# IR_remote.net
KiCad netlist of a schematic drawn in Altium Designer
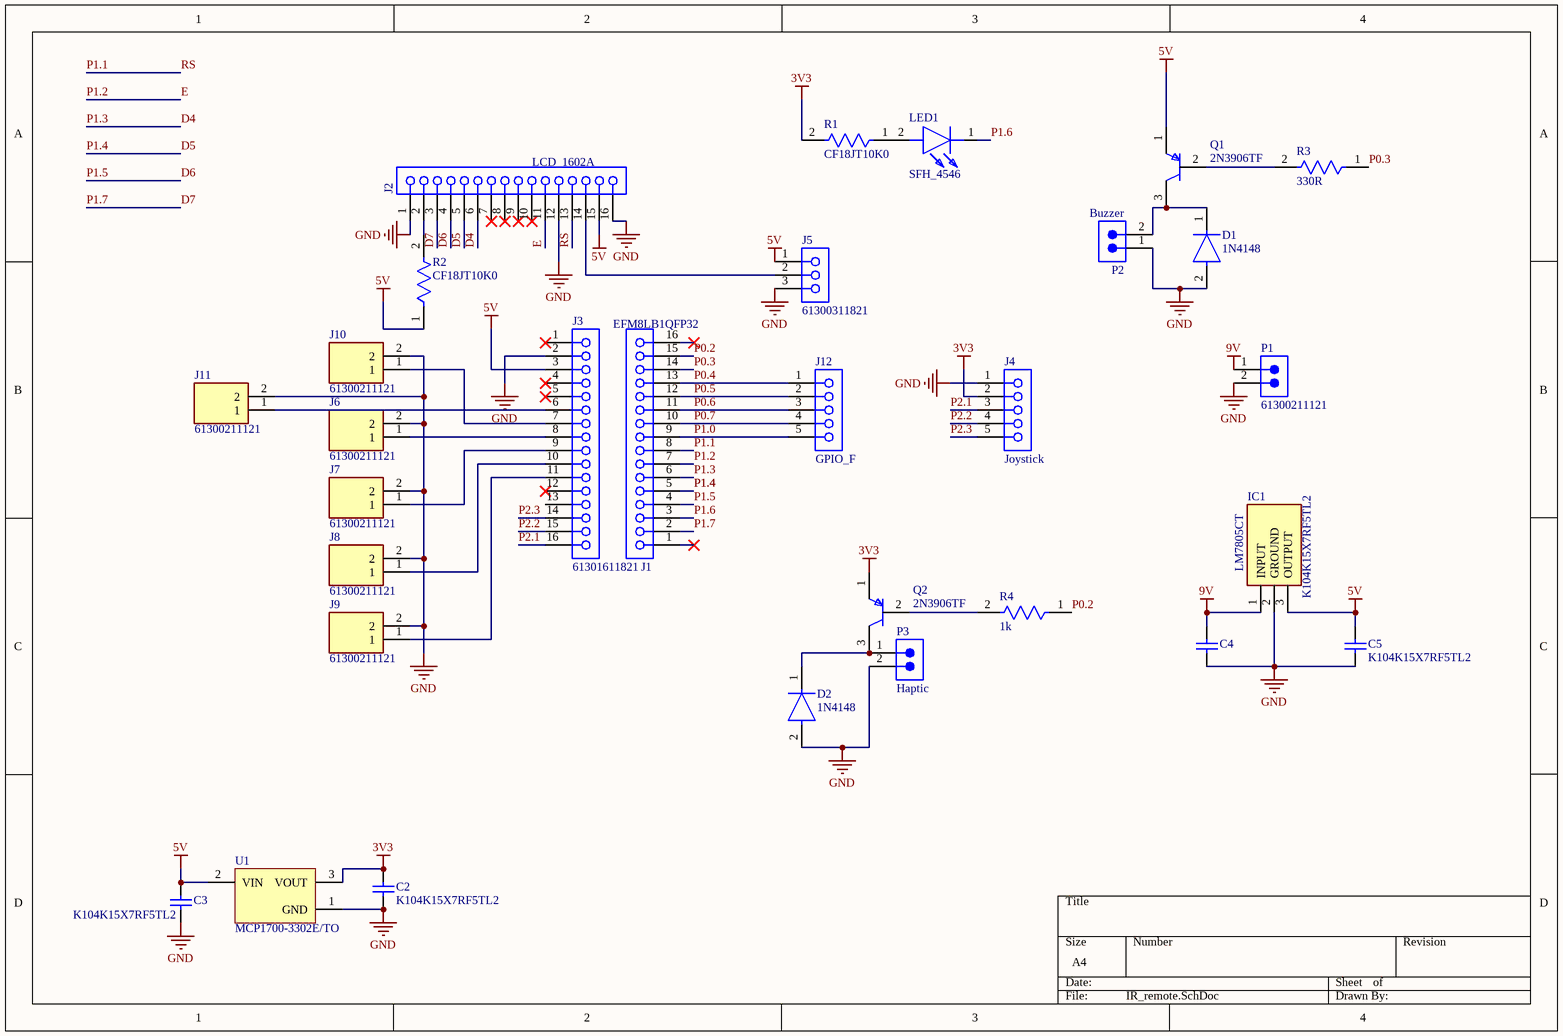
[diagram p0: IR_remote.SchDoc]

(export (version "E")
  (design (tool "Eeschema 10.0.6"))
  (components
    (comp (ref "C2")
      (value "K104K15X7RF5TL2")
      (footprint "VISH-K104K15X7RF5TL2")
      (description "Ceramic Capacitor, 100 nF, +/- 10%, 50 V, -55 to 125 degC, 2-Pin THD, RoHS, Tape and Reel")
      (fields (field (name "MANUFACTURER") "Vishay") (field (name "TOLERANCE") "±10%"))
      (libsource (lib "Altium Content Vault") (part "CAP-NP-2"))
    )
    (comp (ref "C3")
      (value "K104K15X7RF5TL2")
      (footprint "VISH-K104K15X7RF5TL2")
      (description "Ceramic Capacitor, 100 nF, +/- 10%, 50 V, -55 to 125 degC, 2-Pin THD, RoHS, Tape and Reel")
      (fields (field (name "MANUFACTURER") "Vishay") (field (name "TOLERANCE") "±10%"))
      (libsource (lib "Altium Content Vault") (part "CAP-NP-2"))
    )
    (comp (ref "C4")
      (value "K104K15X7RF5TL2")
      (footprint "VISH-K104K15X7RF5TL2")
      (description "Ceramic Capacitor, 100 nF, +/- 10%, 50 V, -55 to 125 degC, 2-Pin THD, RoHS, Tape and Reel")
      (fields (field (name "MANUFACTURER") "Vishay") (field (name "TOLERANCE") "±10%"))
      (libsource (lib "Altium Content Vault") (part "CAP-NP-2"))
    )
    (comp (ref "C5")
      (value "K104K15X7RF5TL2")
      (footprint "VISH-K104K15X7RF5TL2")
      (description "Ceramic Capacitor, 100 nF, +/- 10%, 50 V, -55 to 125 degC, 2-Pin THD, RoHS, Tape and Reel")
      (fields (field (name "MANUFACTURER") "Vishay") (field (name "TOLERANCE") "±10%"))
      (libsource (lib "Altium Content Vault") (part "CAP-NP-2"))
    )
    (comp (ref "D1")
      (value "1N4148")
      (footprint "FP-017AG-MFG")
      (description "DIODE GEN PURP 100V 200MA DO35")
      (fields (field (name "VOLTAGE") "100V"))
      (libsource (lib "Altium Content Vault") (part "d7152d700b627762746794eb795d46e"))
    )
    (comp (ref "D2")
      (value "1N4148")
      (footprint "FP-017AG-MFG")
      (description "DIODE GEN PURP 100V 200MA DO35")
      (fields (field (name "VOLTAGE") "100V"))
      (libsource (lib "Altium Content Vault") (part "d7152d700b627762746794eb795d46e"))
    )
    (comp (ref "IC1")
      (value "LM7805CT")
      (footprint "SamacSys:TO254P470X1028X1955-3P")
      (description "Integrated Circuit")
      (fields (field (name "MOUSER PART NUMBER") "926-LM7805CT"))
      (libsource (lib "*") (part "LM7805CT"))
    )
    (comp (ref "J1")
      (value "EFM8LB1QFP32")
      (footprint "61301611821")
      (description "THT Vertical Socket Header WR-PHD, Pitch 2.54 mm, Single Row, 16 pins")
      (libsource (lib "Altium Content Vault") (part "Header_Female_1R_16P"))
    )
    (comp (ref "J2")
      (value "LCD_1602A")
      (footprint "61301611821")
      (description "THT Vertical Socket Header WR-PHD, Pitch 2.54 mm, Single Row, 16 pins")
      (libsource (lib "Altium Content Vault") (part "Header_Female_1R_16P"))
    )
    (comp (ref "J3")
      (value "61301611821")
      (footprint "61301611821")
      (description "THT Vertical Socket Header WR-PHD, Pitch 2.54 mm, Single Row, 16 pins")
      (libsource (lib "Altium Content Vault") (part "Header_Female_1R_16P"))
    )
    (comp (ref "J4")
      (value "Joystick")
      (footprint "61300511821")
      (description "THT Vertical Socket Header WR-PHD, Pitch 2.54 mm, Single Row, 5 pins")
      (libsource (lib "Altium Content Vault") (part "Header_Female_1R_05P"))
    )
    (comp (ref "J5")
      (value "61300311821")
      (footprint "61300311821")
      (description "Btb Conn, Rcpt, 3Pos, 1Row, 2.54Mm Rohs Compliant: Yes")
      (libsource (lib "Altium Content Vault") (part "Header_Female_1R_03P"))
    )
    (comp (ref "J6")
      (value "61300211121")
      (footprint "SamacSys:HDRV2W110P0X254_1X2_508X254X854P")
      (description "Connector")
      (fields (field (name "MOUSER PART NUMBER") "710-61300211121"))
      (libsource (lib "*") (part "61300211121"))
    )
    (comp (ref "J7")
      (value "61300211121")
      (footprint "SamacSys:HDRV2W110P0X254_1X2_508X254X854P")
      (description "Connector")
      (fields (field (name "MOUSER PART NUMBER") "710-61300211121"))
      (libsource (lib "*") (part "61300211121"))
    )
    (comp (ref "J8")
      (value "61300211121")
      (footprint "SamacSys:HDRV2W110P0X254_1X2_508X254X854P")
      (description "Connector")
      (fields (field (name "MOUSER PART NUMBER") "710-61300211121"))
      (libsource (lib "*") (part "61300211121"))
    )
    (comp (ref "J9")
      (value "61300211121")
      (footprint "SamacSys:HDRV2W110P0X254_1X2_508X254X854P")
      (description "Connector")
      (fields (field (name "MOUSER PART NUMBER") "710-61300211121"))
      (libsource (lib "*") (part "61300211121"))
    )
    (comp (ref "J10")
      (value "61300211121")
      (footprint "SamacSys:HDRV2W110P0X254_1X2_508X254X854P")
      (description "Connector")
      (fields (field (name "MOUSER PART NUMBER") "710-61300211121"))
      (libsource (lib "*") (part "61300211121"))
    )
    (comp (ref "J11")
      (value "61300211121")
      (footprint "SamacSys:HDRV2W110P0X254_1X2_508X254X854P")
      (description "Connector")
      (fields (field (name "MOUSER PART NUMBER") "710-61300211121"))
      (libsource (lib "*") (part "61300211121"))
    )
    (comp (ref "J12")
      (value "GPIO_F")
      (footprint "61300511821")
      (description "THT Vertical Socket Header WR-PHD, Pitch 2.54 mm, Single Row, 5 pins")
      (libsource (lib "Altium Content Vault") (part "Header_Female_1R_05P"))
    )
    (comp (ref "LED1")
      (value "SFH_4546")
      (footprint "SamacSys:SFH_4556P")
      (description "LED")
      (fields
        (field (name "MANUFACTURER_PART_NUMBER") "SFH 4546")
        (field (name "MOUSER PART NUMBER") "720-SFH4546")
      )
      (libsource (lib "*") (part "SFH_4546"))
    )
    (comp (ref "P1")
      (value "61300211121")
      (footprint "61300211121")
      (description "THT Vertical Pin Header WR-PHD, Pitch 2.54 mm, Single Row, 2 pins")
      (libsource (lib "Altium Content Vault") (part "Header_Male_1R_02P"))
    )
    (comp (ref "P2")
      (value "Buzzer")
      (footprint "62000211121")
      (description "THT Vertical Pin Header WR-PHD, Pitch 2.00 mm, Single Row, 2 pins")
      (libsource (lib "Altium Content Vault") (part "Header_Male_1R_02P"))
    )
    (comp (ref "P3")
      (value "Haptic")
      (footprint "62000211121")
      (description "THT Vertical Pin Header WR-PHD, Pitch 2.00 mm, Single Row, 2 pins")
      (libsource (lib "Altium Content Vault") (part "Header_Male_1R_02P"))
    )
    (comp (ref "Q1")
      (value "2N3906TF")
      (footprint "FP-135AR-MFG")
      (description "2N3906TF Small Signal Bipolar Transistor, 0.2A I(C), 40V V(BR)CEO, 1-Element, PNP, Silicon, TO-92")
      (libsource (lib "Altium Content Vault") (part "40d2b7e180a7bcff784209620afba3e"))
    )
    (comp (ref "Q2")
      (value "2N3906TF")
      (footprint "FP-135AR-MFG")
      (description "2N3906TF Small Signal Bipolar Transistor, 0.2A I(C), 40V V(BR)CEO, 1-Element, PNP, Silicon, TO-92")
      (libsource (lib "Altium Content Vault") (part "40d2b7e180a7bcff784209620afba3e"))
    )
    (comp (ref "R1")
      (value "CF18JT10K0")
      (footprint "FP-CF18-MFG")
      (description "RES 10K OHM 1/8W 5% CF AXIAL")
      (fields
        (field (name "MANUFACTURER") "Stackpole Electronics")
        (field (name "OCTOPART") "https://octopart.com/cf18jt10k0-stackpole+electronics-19205642")
      )
      (libsource (lib "Altium Content Vault") (part "1029c3af85768c4190bb7ad29bc67b5"))
    )
    (comp (ref "R2")
      (value "CF18JT10K0")
      (footprint "FP-CF18-MFG")
      (description "RES 10K OHM 1/8W 5% CF AXIAL")
      (fields
        (field (name "MANUFACTURER") "Stackpole Electronics")
        (field (name "OCTOPART") "https://octopart.com/cf18jt10k0-stackpole+electronics-19205642")
      )
      (libsource (lib "Altium Content Vault") (part "1029c3af85768c4190bb7ad29bc67b5"))
    )
    (comp (ref "R3")
      (value "330R")
      (footprint "FP-CF18-MFG")
      (description "RES 10K OHM 1/8W 5% CF AXIAL")
      (fields
        (field (name "MANUFACTURER PART NUMBER") "CF18JT10K0")
        (field (name "MANUFACTURER") "Stackpole Electronics")
      )
      (libsource (lib "Altium Content Vault") (part "1029c3af85768c4190bb7ad29bc67b5"))
    )
    (comp (ref "R4")
      (value "1k")
      (footprint "FP-CF18-MFG")
      (description "RES 10K OHM 1/8W 5% CF AXIAL")
      (fields
        (field (name "MANUFACTURER PART NUMBER") "CF18JT10K0")
        (field (name "MANUFACTURER") "Stackpole Electronics")
      )
      (libsource (lib "Altium Content Vault") (part "1029c3af85768c4190bb7ad29bc67b5"))
    )
    (comp (ref "U1")
      (value "MCP1700-3302E/TO")
      (footprint "TO-92-TO3")
      (description "Low Quiescent Current LDO, 3-Pin TO-92, Extended TemperatureBAG")
      (libsource (lib "Altium Content Vault") (part "PM-LINEREG-MCP1700-IL3B"))
    )
  )
  (nets
    (net (code "1") (name "/D4") (class "Default")
      (node (ref "J1") (pin "6") (pinfunction "6_6") (pintype "passive"))
      (node (ref "J2") (pin "6") (pinfunction "6_6") (pintype "passive"))
    )
    (net (code "2") (name "/D5") (class "Default")
      (node (ref "J1") (pin "5") (pinfunction "5_5") (pintype "passive"))
      (node (ref "J2") (pin "5") (pinfunction "5_5") (pintype "passive"))
    )
    (net (code "3") (name "/D6") (class "Default")
      (node (ref "J1") (pin "4") (pinfunction "4_4") (pintype "passive"))
      (node (ref "J2") (pin "4") (pinfunction "4_4") (pintype "passive"))
    )
    (net (code "4") (name "/D7") (class "Default")
      (node (ref "J1") (pin "2") (pinfunction "2_2") (pintype "passive"))
      (node (ref "J2") (pin "3") (pinfunction "3_3") (pintype "passive"))
    )
    (net (code "5") (name "/E") (class "Default")
      (node (ref "J1") (pin "7") (pinfunction "7_7") (pintype "passive"))
      (node (ref "J2") (pin "11") (pinfunction "11_11") (pintype "passive"))
    )
    (net (code "6") (name "/P0.2") (class "Default")
      (node (ref "J1") (pin "15") (pinfunction "15_15") (pintype "passive"))
      (node (ref "R4") (pin "1") (pinfunction "1_1") (pintype "passive"))
    )
    (net (code "7") (name "/P0.3") (class "Default")
      (node (ref "J1") (pin "14") (pinfunction "14_14") (pintype "passive"))
      (node (ref "R3") (pin "1") (pinfunction "1_1") (pintype "passive"))
    )
    (net (code "8") (name "/P0.4") (class "Default")
      (node (ref "J1") (pin "13") (pinfunction "13_13") (pintype "passive"))
      (node (ref "J12") (pin "1") (pinfunction "1_1") (pintype "passive"))
    )
    (net (code "9") (name "/P0.5") (class "Default")
      (node (ref "J1") (pin "12") (pinfunction "12_12") (pintype "passive"))
      (node (ref "J12") (pin "2") (pinfunction "2_2") (pintype "passive"))
    )
    (net (code "10") (name "/P0.6") (class "Default")
      (node (ref "J1") (pin "11") (pinfunction "11_11") (pintype "passive"))
      (node (ref "J12") (pin "3") (pinfunction "3_3") (pintype "passive"))
    )
    (net (code "11") (name "/P0.7") (class "Default")
      (node (ref "J1") (pin "10") (pinfunction "10_10") (pintype "passive"))
      (node (ref "J12") (pin "4") (pinfunction "4_4") (pintype "passive"))
    )
    (net (code "12") (name "/P1.0") (class "Default")
      (node (ref "J1") (pin "9") (pinfunction "9_9") (pintype "passive"))
      (node (ref "J12") (pin "5") (pinfunction "5_5") (pintype "passive"))
    )
    (net (code "13") (name "/P1.1") (class "Default")
      (node (ref "J1") (pin "8") (pinfunction "8_8") (pintype "passive"))
      (node (ref "J2") (pin "13") (pinfunction "13_13") (pintype "passive"))
    )
    (net (code "14") (name "/P1.6") (class "Default")
      (node (ref "J1") (pin "3") (pinfunction "3_3") (pintype "passive"))
      (node (ref "LED1") (pin "1") (pinfunction "K_1") (pintype "passive"))
    )
    (net (code "15") (name "/P2.1") (class "Default")
      (node (ref "J3") (pin "16") (pinfunction "16_16") (pintype "passive"))
      (node (ref "J4") (pin "3") (pinfunction "3_3") (pintype "passive"))
    )
    (net (code "16") (name "/P2.2") (class "Default")
      (node (ref "J3") (pin "15") (pinfunction "15_15") (pintype "passive"))
      (node (ref "J4") (pin "4") (pinfunction "4_4") (pintype "passive"))
    )
    (net (code "17") (name "/P2.3") (class "Default")
      (node (ref "J3") (pin "14") (pinfunction "14_14") (pintype "passive"))
      (node (ref "J4") (pin "5") (pinfunction "5_5") (pintype "passive"))
    )
    (net (code "18") (name "3V3") (class "Default")
      (node (ref "C2") (pin "1") (pinfunction "1_1") (pintype "passive"))
      (node (ref "J4") (pin "2") (pinfunction "2_2") (pintype "passive"))
      (node (ref "Q2") (pin "1") (pinfunction "E_1") (pintype "passive"))
      (node (ref "R1") (pin "2") (pinfunction "2_2") (pintype "passive"))
      (node (ref "U1") (pin "3") (pinfunction "VOUT_3") (pintype "power_in"))
    )
    (net (code "19") (name "5V") (class "Default")
      (node (ref "C3") (pin "1") (pinfunction "1_1") (pintype "passive"))
      (node (ref "C5") (pin "2") (pinfunction "2_2") (pintype "passive"))
      (node (ref "IC1") (pin "3") (pinfunction "OUTPUT_3") (pintype "passive"))
      (node (ref "J2") (pin "15") (pinfunction "15_15") (pintype "passive"))
      (node (ref "J3") (pin "3") (pinfunction "3_3") (pintype "passive"))
      (node (ref "J5") (pin "1") (pinfunction "1_1") (pintype "passive"))
      (node (ref "Q1") (pin "1") (pinfunction "E_1") (pintype "passive"))
      (node (ref "R2") (pin "1") (pinfunction "1_1") (pintype "passive"))
      (node (ref "U1") (pin "2") (pinfunction "VIN_2") (pintype "power_in"))
    )
    (net (code "20") (name "9V") (class "Default")
      (node (ref "C4") (pin "2") (pinfunction "2_2") (pintype "passive"))
      (node (ref "IC1") (pin "1") (pinfunction "INPUT_1") (pintype "passive"))
      (node (ref "P1") (pin "1") (pinfunction "1_1") (pintype "passive"))
    )
    (net (code "21") (name "GND") (class "Default")
      (node (ref "C2") (pin "2") (pinfunction "2_2") (pintype "passive"))
      (node (ref "C3") (pin "2") (pinfunction "2_2") (pintype "passive"))
      (node (ref "C4") (pin "1") (pinfunction "1_1") (pintype "passive"))
      (node (ref "C5") (pin "1") (pinfunction "1_1") (pintype "passive"))
      (node (ref "D1") (pin "2") (pinfunction "A_2") (pintype "passive"))
      (node (ref "D2") (pin "2") (pinfunction "A_2") (pintype "passive"))
      (node (ref "IC1") (pin "2") (pinfunction "GROUND_2") (pintype "passive"))
      (node (ref "J10") (pin "2") (pinfunction "2_2") (pintype "passive"))
      (node (ref "J11") (pin "2") (pinfunction "2_2") (pintype "passive"))
      (node (ref "J2") (pin "1") (pinfunction "1_1") (pintype "passive"))
      (node (ref "J2") (pin "12") (pinfunction "12_12") (pintype "passive"))
      (node (ref "J2") (pin "16") (pinfunction "16_16") (pintype "passive"))
      (node (ref "J3") (pin "2") (pinfunction "2_2") (pintype "passive"))
      (node (ref "J4") (pin "1") (pinfunction "1_1") (pintype "passive"))
      (node (ref "J5") (pin "3") (pinfunction "3_3") (pintype "passive"))
      (node (ref "J6") (pin "2") (pinfunction "2_2") (pintype "passive"))
      (node (ref "J7") (pin "2") (pinfunction "2_2") (pintype "passive"))
      (node (ref "J8") (pin "2") (pinfunction "2_2") (pintype "passive"))
      (node (ref "J9") (pin "2") (pinfunction "2_2") (pintype "passive"))
      (node (ref "P1") (pin "2") (pinfunction "2_2") (pintype "passive"))
      (node (ref "P2") (pin "1") (pinfunction "1_1") (pintype "passive"))
      (node (ref "P3") (pin "2") (pinfunction "2_2") (pintype "passive"))
      (node (ref "U1") (pin "1") (pinfunction "GND_1") (pintype "power_in"))
    )
    (net (code "22") (name "Net-(D1-C)") (class "Default")
      (node (ref "D1") (pin "1") (pinfunction "C_1") (pintype "passive"))
      (node (ref "P2") (pin "2") (pinfunction "2_2") (pintype "passive"))
      (node (ref "Q1") (pin "3") (pinfunction "C_3") (pintype "passive"))
    )
    (net (code "23") (name "Net-(D2-C)") (class "Default")
      (node (ref "D2") (pin "1") (pinfunction "C_1") (pintype "passive"))
      (node (ref "P3") (pin "1") (pinfunction "1_1") (pintype "passive"))
      (node (ref "Q2") (pin "3") (pinfunction "C_3") (pintype "passive"))
    )
    (net (code "24") (name "Net-(J2-Pad2)") (class "Default")
      (node (ref "J2") (pin "2") (pinfunction "2_2") (pintype "passive"))
      (node (ref "R2") (pin "2") (pinfunction "2_2") (pintype "passive"))
    )
    (net (code "25") (name "Net-(J2-Pad14)") (class "Default")
      (node (ref "J2") (pin "14") (pinfunction "14_14") (pintype "passive"))
      (node (ref "J5") (pin "2") (pinfunction "2_2") (pintype "passive"))
    )
    (net (code "26") (name "Net-(J3-Pad8)") (class "Default")
      (node (ref "J3") (pin "8") (pinfunction "8_8") (pintype "passive"))
      (node (ref "J6") (pin "1") (pinfunction "1_1") (pintype "passive"))
    )
    (net (code "27") (name "Net-(J3-Pad9)") (class "Default")
      (node (ref "J3") (pin "9") (pinfunction "9_9") (pintype "passive"))
      (node (ref "J7") (pin "1") (pinfunction "1_1") (pintype "passive"))
    )
    (net (code "28") (name "Net-(J3-Pad10)") (class "Default")
      (node (ref "J3") (pin "10") (pinfunction "10_10") (pintype "passive"))
      (node (ref "J8") (pin "1") (pinfunction "1_1") (pintype "passive"))
    )
    (net (code "29") (name "Net-(J3-Pad11)") (class "Default")
      (node (ref "J3") (pin "11") (pinfunction "11_11") (pintype "passive"))
      (node (ref "J9") (pin "1") (pinfunction "1_1") (pintype "passive"))
    )
    (net (code "30") (name "Net-(J10-Pad1)") (class "Default")
      (node (ref "J10") (pin "1") (pinfunction "1_1") (pintype "passive"))
      (node (ref "J3") (pin "7") (pinfunction "7_7") (pintype "passive"))
    )
    (net (code "31") (name "Net-(J11-Pad1)") (class "Default")
      (node (ref "J11") (pin "1") (pinfunction "1_1") (pintype "passive"))
      (node (ref "J3") (pin "6") (pinfunction "6_6") (pintype "passive"))
    )
    (net (code "32") (name "Net-(LED1-A)") (class "Default")
      (node (ref "LED1") (pin "2") (pinfunction "A_2") (pintype "passive"))
      (node (ref "R1") (pin "1") (pinfunction "1_1") (pintype "passive"))
    )
    (net (code "33") (name "Net-(Q1-B)") (class "Default")
      (node (ref "Q1") (pin "2") (pinfunction "B_2") (pintype "passive"))
      (node (ref "R3") (pin "2") (pinfunction "2_2") (pintype "passive"))
    )
    (net (code "34") (name "Net-(Q2-B)") (class "Default")
      (node (ref "Q2") (pin "2") (pinfunction "B_2") (pintype "passive"))
      (node (ref "R4") (pin "2") (pinfunction "2_2") (pintype "passive"))
    )
    (net (code "35") (name "unconnected-(J1-Pad1)") (class "Default")
      (node (ref "J1") (pin "1") (pinfunction "1_1") (pintype "passive+no_connect"))
    )
    (net (code "36") (name "unconnected-(J1-Pad16)") (class "Default")
      (node (ref "J1") (pin "16") (pinfunction "16_16") (pintype "passive+no_connect"))
    )
    (net (code "37") (name "unconnected-(J2-Pad7)") (class "Default")
      (node (ref "J2") (pin "7") (pinfunction "7_7") (pintype "passive+no_connect"))
    )
    (net (code "38") (name "unconnected-(J2-Pad8)") (class "Default")
      (node (ref "J2") (pin "8") (pinfunction "8_8") (pintype "passive+no_connect"))
    )
    (net (code "39") (name "unconnected-(J2-Pad9)") (class "Default")
      (node (ref "J2") (pin "9") (pinfunction "9_9") (pintype "passive+no_connect"))
    )
    (net (code "40") (name "unconnected-(J2-Pad10)") (class "Default")
      (node (ref "J2") (pin "10") (pinfunction "10_10") (pintype "passive+no_connect"))
    )
    (net (code "41") (name "unconnected-(J3-Pad1)") (class "Default")
      (node (ref "J3") (pin "1") (pinfunction "1_1") (pintype "passive+no_connect"))
    )
    (net (code "42") (name "unconnected-(J3-Pad4)") (class "Default")
      (node (ref "J3") (pin "4") (pinfunction "4_4") (pintype "passive+no_connect"))
    )
    (net (code "43") (name "unconnected-(J3-Pad5)") (class "Default")
      (node (ref "J3") (pin "5") (pinfunction "5_5") (pintype "passive+no_connect"))
    )
    (net (code "44") (name "unconnected-(J3-Pad12)") (class "Default")
      (node (ref "J3") (pin "12") (pinfunction "12_12") (pintype "passive+no_connect"))
    )
    (net (code "45") (name "unconnected-(J3-Pad13)") (class "Default")
      (node (ref "J3") (pin "13") (pinfunction "13_13") (pintype "passive"))
    )
  )
)
